# Serial_Output_Ports.net
KiCad netlist of a schematic drawn in Altium Designer
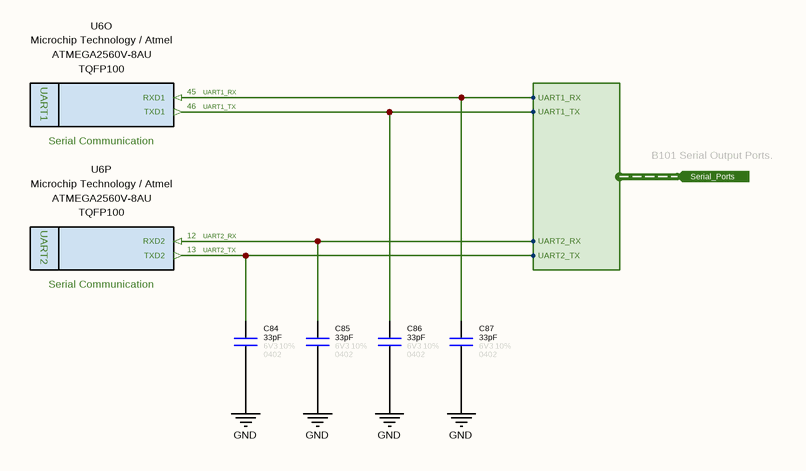
[diagram p0: Serial Output Ports.SchDoc]

(export (version "E")
  (design (tool "Eeschema 10.0.6"))
  (components
    (comp (ref "C84")
      (value "33pF")
      (footprint "CAPACITOR_0402")
      (description "Capacitor - 33pF [0402] (Ceramic)")
      (fields
        (field (name "MANUFACTURER PART NUMBER") "C0402C330J9RACAUTO")
        (field (name "TOLERANCE") "10%")
        (field (name "CASE") "0402")
        (field (name "VOLTAGE") "6V3")
      )
      (libsource (lib "P101DA_Library") (part "Capacitor - 33pF [0402-6V3]"))
    )
    (comp (ref "C85")
      (value "33pF")
      (footprint "CAPACITOR_0402")
      (description "Capacitor - 33pF [0402] (Ceramic)")
      (fields
        (field (name "MANUFACTURER PART NUMBER") "C0402C330J9RACAUTO")
        (field (name "TOLERANCE") "10%")
        (field (name "CASE") "0402")
        (field (name "VOLTAGE") "6V3")
      )
      (libsource (lib "P101DA_Library") (part "Capacitor - 33pF [0402-6V3]"))
    )
    (comp (ref "C86")
      (value "33pF")
      (footprint "CAPACITOR_0402")
      (description "Capacitor - 33pF [0402] (Ceramic)")
      (fields
        (field (name "MANUFACTURER PART NUMBER") "C0402C330J9RACAUTO")
        (field (name "TOLERANCE") "10%")
        (field (name "CASE") "0402")
        (field (name "VOLTAGE") "6V3")
      )
      (libsource (lib "P101DA_Library") (part "Capacitor - 33pF [0402-6V3]"))
    )
    (comp (ref "C87")
      (value "33pF")
      (footprint "CAPACITOR_0402")
      (description "Capacitor - 33pF [0402] (Ceramic)")
      (fields
        (field (name "MANUFACTURER PART NUMBER") "C0402C330J9RACAUTO")
        (field (name "TOLERANCE") "10%")
        (field (name "CASE") "0402")
        (field (name "VOLTAGE") "6V3")
      )
      (libsource (lib "P101DA_Library") (part "Capacitor - 33pF [0402-6V3]"))
    )
    (comp (ref "U6")
      (value "ATMEGA2560V-8AU")
      (footprint "TQFP-100")
      (description "ATmega Series 256 KB Flash 8 KB SRAM 8 MHz 8-Bit Microcontroller - TQFP-100")
      (fields
        (field (name "MANUFACTURER NAME") "Microchip Technology / Atmel")
        (field (name "MANUFACTURER PART NUMBER") "ATMEGA2560V-8AU")
        (field (name "CASE") "TQFP100")
      )
      (libsource (lib "P101DA_Library") (part "IC - AtMega2560V-8AU"))
    )
  )
  (nets
    (net (code "2") (name "/UART1_RX") (class "Default")
      (node (ref "C87") (pin "2") (pinfunction "2_2") (pintype "passive"))
      (node (ref "U6") (pin "45") (pinfunction "RXD1_45") (pintype "input"))
    )
    (net (code "3") (name "/UART1_TX") (class "Default")
      (node (ref "C86") (pin "2") (pinfunction "2_2") (pintype "passive"))
      (node (ref "U6") (pin "46") (pinfunction "TXD1_46") (pintype "output"))
    )
    (net (code "4") (name "/UART2_RX") (class "Default")
      (node (ref "C85") (pin "2") (pinfunction "2_2") (pintype "passive"))
      (node (ref "U6") (pin "12") (pinfunction "RXD2_12") (pintype "input"))
    )
    (net (code "5") (name "/UART2_TX") (class "Default")
      (node (ref "C84") (pin "2") (pinfunction "2_2") (pintype "passive"))
      (node (ref "U6") (pin "13") (pinfunction "TXD2_13") (pintype "output"))
    )
    (net (code "7") (name "GND") (class "Default")
      (node (ref "C84") (pin "1") (pinfunction "1_1") (pintype "passive"))
      (node (ref "C85") (pin "1") (pinfunction "1_1") (pintype "passive"))
      (node (ref "C86") (pin "1") (pinfunction "1_1") (pintype "passive"))
      (node (ref "C87") (pin "1") (pinfunction "1_1") (pintype "passive"))
    )
  )
)
